# MAVBoard_Pro.net
KiCad netlist of a schematic drawn in EAGLE
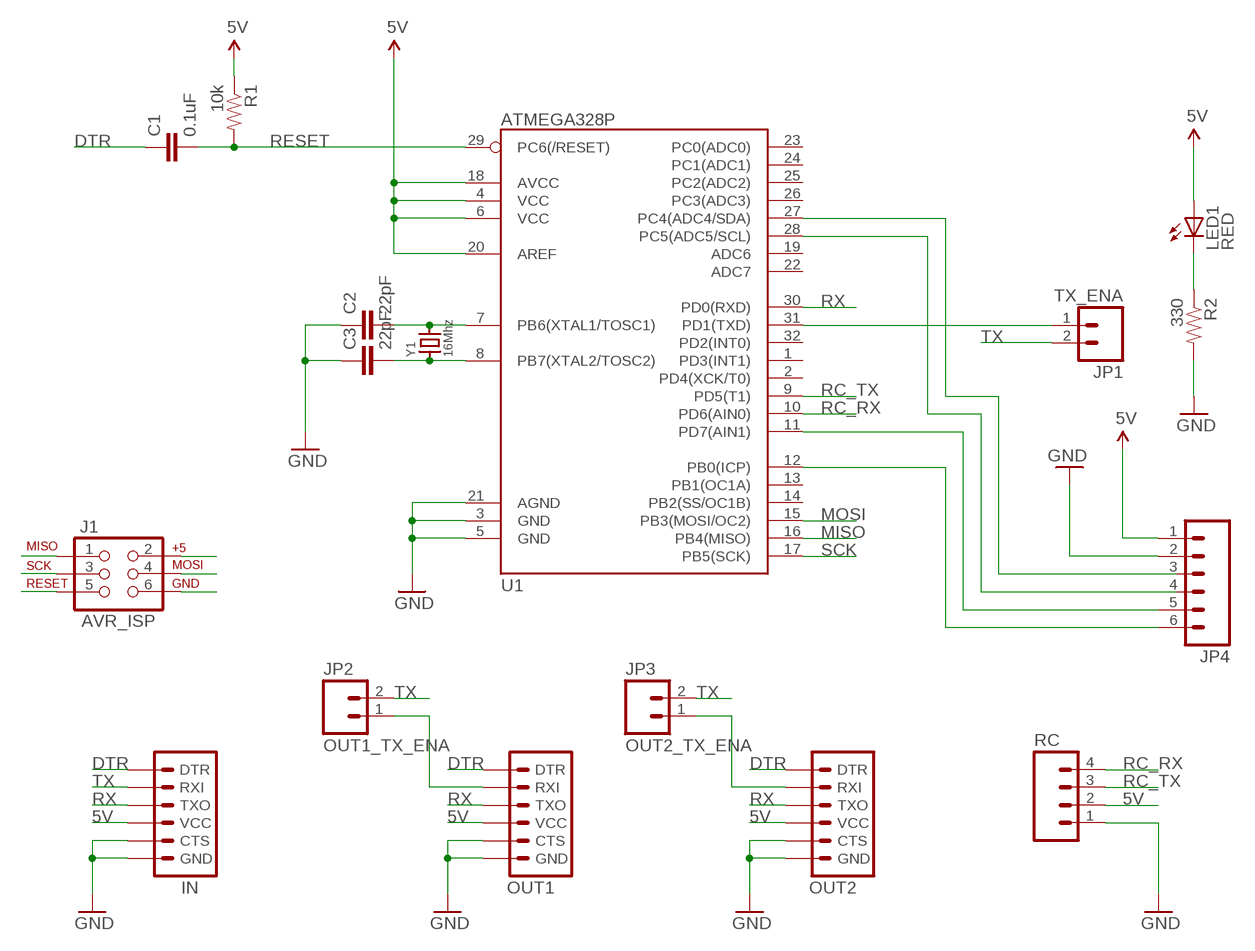
[diagram p0: schematic, sheet 1]

(export (version "E")
  (design (tool "Eeschema 10.0.6"))
  (components
    (comp (ref "C1")
      (value "0.1uF")
      (footprint "eagle-import:0603-CAP")
      (libsource (lib "eagle-import") (part "CAP0603-CAP"))
    )
    (comp (ref "C2")
      (value "22pF")
      (footprint "eagle-import:0603-CAP")
      (libsource (lib "eagle-import") (part "CAP0603-CAP"))
    )
    (comp (ref "C3")
      (value "22pF")
      (footprint "eagle-import:0603-CAP")
      (libsource (lib "eagle-import") (part "CAP0603-CAP"))
    )
    (comp (ref "IN")
      (value "ARDUINO_SERIAL_PROGRAMPTH")
      (footprint "eagle-import:1X06")
      (libsource (lib "eagle-import") (part "ARDUINO_SERIAL_PROGRAMPTH"))
    )
    (comp (ref "J1")
      (value "AVR_ISP")
      (footprint "eagle-import:2X3")
      (libsource (lib "eagle-import") (part "AVR_SPI_PRG_6PTH"))
    )
    (comp (ref "JP1")
      (value "TX_ENA")
      (footprint "eagle-import:1X02")
      (libsource (lib "eagle-import") (part "M02PTH"))
    )
    (comp (ref "JP2")
      (value "OUT1_TX_ENA")
      (footprint "eagle-import:1X02")
      (libsource (lib "eagle-import") (part "M02PTH"))
    )
    (comp (ref "JP3")
      (value "OUT2_TX_ENA")
      (footprint "eagle-import:1X02")
      (libsource (lib "eagle-import") (part "M02PTH"))
    )
    (comp (ref "JP4")
      (value "M06SIP")
      (footprint "eagle-import:1X06")
      (libsource (lib "eagle-import") (part "M06SIP"))
    )
    (comp (ref "LED1")
      (value "RED")
      (footprint "eagle-import:LED-0603")
      (libsource (lib "eagle-import") (part "LED0603"))
    )
    (comp (ref "OUT1")
      (value "ARDUINO_SERIAL_PROGRAMPTH")
      (footprint "eagle-import:1X06")
      (libsource (lib "eagle-import") (part "ARDUINO_SERIAL_PROGRAMPTH"))
    )
    (comp (ref "OUT2")
      (value "ARDUINO_SERIAL_PROGRAMPTH")
      (footprint "eagle-import:1X06")
      (libsource (lib "eagle-import") (part "ARDUINO_SERIAL_PROGRAMPTH"))
    )
    (comp (ref "R1")
      (value "10k")
      (footprint "eagle-import:0603-RES")
      (libsource (lib "eagle-import") (part "RESISTOR0603-RES"))
    )
    (comp (ref "R2")
      (value "330")
      (footprint "eagle-import:0603-RES")
      (libsource (lib "eagle-import") (part "RESISTOR0603-RES"))
    )
    (comp (ref "RC")
      (value "M04PTH")
      (footprint "eagle-import:1X04")
      (libsource (lib "eagle-import") (part "M04PTH"))
    )
    (comp (ref "U1")
      (value "ATMEGA328P")
      (footprint "eagle-import:TQFP32-08")
      (libsource (lib "eagle-import") (part "ATMEGA328_SMT"))
    )
    (comp (ref "Y1")
      (value "16Mhz")
      (footprint "eagle-import:CRYSTALSMD_5X3.2MM")
      (libsource (lib "eagle-import") (part "CRYSTAL5X3.2"))
    )
  )
  (nets
    (net (code "1") (name "/DTR") (class "Default")
      (node (ref "C1") (pin "1") (pinfunction "1_1") (pintype "passive"))
      (node (ref "IN") (pin "1") (pinfunction "DTR_1") (pintype "passive"))
      (node (ref "OUT1") (pin "1") (pinfunction "DTR_1") (pintype "passive"))
      (node (ref "OUT2") (pin "1") (pinfunction "DTR_1") (pintype "passive"))
    )
    (net (code "2") (name "/MISO") (class "Default")
      (node (ref "J1") (pin "1") (pinfunction "1_1") (pintype "passive"))
      (node (ref "U1") (pin "16") (pinfunction "PB4(MISO)_16") (pintype "bidirectional"))
    )
    (net (code "3") (name "/MOSI") (class "Default")
      (node (ref "J1") (pin "4") (pinfunction "4_4") (pintype "passive"))
      (node (ref "U1") (pin "15") (pinfunction "PB3(MOSI/OC2)_15") (pintype "bidirectional"))
    )
    (net (code "4") (name "/RC_RX") (class "Default")
      (node (ref "RC") (pin "4") (pinfunction "4_4") (pintype "passive"))
      (node (ref "U1") (pin "10") (pinfunction "PD6(AIN0)_10") (pintype "bidirectional"))
    )
    (net (code "5") (name "/RC_TX") (class "Default")
      (node (ref "RC") (pin "3") (pinfunction "3_3") (pintype "passive"))
      (node (ref "U1") (pin "9") (pinfunction "PD5(T1)_9") (pintype "bidirectional"))
    )
    (net (code "6") (name "/RESET") (class "Default")
      (node (ref "C1") (pin "2") (pinfunction "2_2") (pintype "passive"))
      (node (ref "J1") (pin "5") (pinfunction "5_5") (pintype "passive"))
      (node (ref "R1") (pin "2") (pinfunction "2_2") (pintype "passive"))
      (node (ref "U1") (pin "29") (pinfunction "PC6(/RESET)_29") (pintype "bidirectional"))
    )
    (net (code "7") (name "/RX") (class "Default")
      (node (ref "IN") (pin "3") (pinfunction "TXO_3") (pintype "passive"))
      (node (ref "OUT1") (pin "3") (pinfunction "TXO_3") (pintype "passive"))
      (node (ref "OUT2") (pin "3") (pinfunction "TXO_3") (pintype "passive"))
      (node (ref "U1") (pin "30") (pinfunction "PD0(RXD)_30") (pintype "bidirectional"))
    )
    (net (code "8") (name "/SCK") (class "Default")
      (node (ref "J1") (pin "3") (pinfunction "3_3") (pintype "passive"))
      (node (ref "U1") (pin "17") (pinfunction "PB5(SCK)_17") (pintype "bidirectional"))
    )
    (net (code "9") (name "/TX") (class "Default")
      (node (ref "IN") (pin "2") (pinfunction "RXI_2") (pintype "passive"))
      (node (ref "JP1") (pin "2") (pinfunction "2_2") (pintype "passive"))
      (node (ref "JP2") (pin "2") (pinfunction "2_2") (pintype "passive"))
      (node (ref "JP3") (pin "2") (pinfunction "2_2") (pintype "passive"))
    )
    (net (code "10") (name "5V") (class "Default")
      (node (ref "IN") (pin "4") (pinfunction "VCC_4") (pintype "passive"))
      (node (ref "J1") (pin "2") (pinfunction "2_2") (pintype "passive"))
      (node (ref "JP4") (pin "1") (pinfunction "1_1") (pintype "passive"))
      (node (ref "LED1") (pin "A") (pinfunction "A_A") (pintype "passive"))
      (node (ref "OUT1") (pin "4") (pinfunction "VCC_4") (pintype "passive"))
      (node (ref "OUT2") (pin "4") (pinfunction "VCC_4") (pintype "passive"))
      (node (ref "R1") (pin "1") (pinfunction "1_1") (pintype "passive"))
      (node (ref "RC") (pin "2") (pinfunction "2_2") (pintype "passive"))
      (node (ref "U1") (pin "18") (pinfunction "AVCC_18") (pintype "bidirectional"))
      (node (ref "U1") (pin "20") (pinfunction "AREF_20") (pintype "bidirectional"))
      (node (ref "U1") (pin "4") (pinfunction "VCC_4") (pintype "bidirectional"))
      (node (ref "U1") (pin "6") (pinfunction "VCC_6") (pintype "bidirectional"))
    )
    (net (code "11") (name "GND") (class "Default")
      (node (ref "C2") (pin "1") (pinfunction "1_1") (pintype "passive"))
      (node (ref "C3") (pin "1") (pinfunction "1_1") (pintype "passive"))
      (node (ref "IN") (pin "5") (pinfunction "CTS_5") (pintype "passive"))
      (node (ref "IN") (pin "6") (pinfunction "GND_6") (pintype "passive"))
      (node (ref "J1") (pin "6") (pinfunction "6_6") (pintype "passive"))
      (node (ref "JP4") (pin "2") (pinfunction "2_2") (pintype "passive"))
      (node (ref "OUT1") (pin "5") (pinfunction "CTS_5") (pintype "passive"))
      (node (ref "OUT1") (pin "6") (pinfunction "GND_6") (pintype "passive"))
      (node (ref "OUT2") (pin "5") (pinfunction "CTS_5") (pintype "passive"))
      (node (ref "OUT2") (pin "6") (pinfunction "GND_6") (pintype "passive"))
      (node (ref "R2") (pin "2") (pinfunction "2_2") (pintype "passive"))
      (node (ref "RC") (pin "1") (pinfunction "1_1") (pintype "passive"))
      (node (ref "U1") (pin "21") (pinfunction "AGND_21") (pintype "bidirectional"))
      (node (ref "U1") (pin "3") (pinfunction "GND_3") (pintype "bidirectional"))
      (node (ref "U1") (pin "5") (pinfunction "GND_5") (pintype "bidirectional"))
    )
    (net (code "12") (name "Net-(LED1-PadC)") (class "Default")
      (node (ref "LED1") (pin "C") (pinfunction "C_C") (pintype "passive"))
      (node (ref "R2") (pin "1") (pinfunction "1_1") (pintype "passive"))
    )
    (net (code "13") (name "Net-(OUT1-RXI)") (class "Default")
      (node (ref "JP2") (pin "1") (pinfunction "1_1") (pintype "passive"))
      (node (ref "OUT1") (pin "2") (pinfunction "RXI_2") (pintype "passive"))
    )
    (net (code "14") (name "Net-(OUT2-RXI)") (class "Default")
      (node (ref "JP3") (pin "1") (pinfunction "1_1") (pintype "passive"))
      (node (ref "OUT2") (pin "2") (pinfunction "RXI_2") (pintype "passive"))
    )
    (net (code "15") (name "Net-(U1-PB0(ICP))") (class "Default")
      (node (ref "JP4") (pin "6") (pinfunction "6_6") (pintype "passive"))
      (node (ref "U1") (pin "12") (pinfunction "PB0(ICP)_12") (pintype "bidirectional"))
    )
    (net (code "16") (name "Net-(U1-PB6(XTAL1{slash}TOSC1))") (class "Default")
      (node (ref "C2") (pin "2") (pinfunction "2_2") (pintype "passive"))
      (node (ref "U1") (pin "7") (pinfunction "PB6(XTAL1/TOSC1)_7") (pintype "bidirectional"))
      (node (ref "Y1") (pin "PIN3") (pinfunction "PIN3_PIN3") (pintype "bidirectional"))
    )
    (net (code "17") (name "Net-(U1-PB7(XTAL2{slash}TOSC2))") (class "Default")
      (node (ref "C3") (pin "2") (pinfunction "2_2") (pintype "passive"))
      (node (ref "U1") (pin "8") (pinfunction "PB7(XTAL2/TOSC2)_8") (pintype "bidirectional"))
      (node (ref "Y1") (pin "PIN1") (pinfunction "PIN1_PIN1") (pintype "bidirectional"))
    )
    (net (code "18") (name "Net-(U1-PC4(ADC4{slash}SDA))") (class "Default")
      (node (ref "JP4") (pin "3") (pinfunction "3_3") (pintype "passive"))
      (node (ref "U1") (pin "27") (pinfunction "PC4(ADC4/SDA)_27") (pintype "bidirectional"))
    )
    (net (code "19") (name "Net-(U1-PC5(ADC5{slash}SCL))") (class "Default")
      (node (ref "JP4") (pin "4") (pinfunction "4_4") (pintype "passive"))
      (node (ref "U1") (pin "28") (pinfunction "PC5(ADC5/SCL)_28") (pintype "bidirectional"))
    )
    (net (code "20") (name "Net-(U1-PD1(TXD))") (class "Default")
      (node (ref "JP1") (pin "1") (pinfunction "1_1") (pintype "passive"))
      (node (ref "U1") (pin "31") (pinfunction "PD1(TXD)_31") (pintype "bidirectional"))
    )
    (net (code "21") (name "Net-(U1-PD7(AIN1))") (class "Default")
      (node (ref "JP4") (pin "5") (pinfunction "5_5") (pintype "passive"))
      (node (ref "U1") (pin "11") (pinfunction "PD7(AIN1)_11") (pintype "bidirectional"))
    )
    (net (code "22") (name "unconnected-(U1-ADC6-Pad19)") (class "Default")
      (node (ref "U1") (pin "19") (pinfunction "ADC6_19") (pintype "bidirectional"))
    )
    (net (code "23") (name "unconnected-(U1-ADC7-Pad22)") (class "Default")
      (node (ref "U1") (pin "22") (pinfunction "ADC7_22") (pintype "bidirectional"))
    )
    (net (code "24") (name "unconnected-(U1-PB1(OC1A)-Pad13)") (class "Default")
      (node (ref "U1") (pin "13") (pinfunction "PB1(OC1A)_13") (pintype "bidirectional"))
    )
    (net (code "25") (name "unconnected-(U1-PB2(SS{slash}OC1B)-Pad14)") (class "Default")
      (node (ref "U1") (pin "14") (pinfunction "PB2(SS/OC1B)_14") (pintype "bidirectional"))
    )
    (net (code "26") (name "unconnected-(U1-PC0(ADC0)-Pad23)") (class "Default")
      (node (ref "U1") (pin "23") (pinfunction "PC0(ADC0)_23") (pintype "bidirectional"))
    )
    (net (code "27") (name "unconnected-(U1-PC1(ADC1)-Pad24)") (class "Default")
      (node (ref "U1") (pin "24") (pinfunction "PC1(ADC1)_24") (pintype "bidirectional"))
    )
    (net (code "28") (name "unconnected-(U1-PC2(ADC2)-Pad25)") (class "Default")
      (node (ref "U1") (pin "25") (pinfunction "PC2(ADC2)_25") (pintype "bidirectional"))
    )
    (net (code "29") (name "unconnected-(U1-PC3(ADC3)-Pad26)") (class "Default")
      (node (ref "U1") (pin "26") (pinfunction "PC3(ADC3)_26") (pintype "bidirectional"))
    )
    (net (code "30") (name "unconnected-(U1-PD2(INT0)-Pad32)") (class "Default")
      (node (ref "U1") (pin "32") (pinfunction "PD2(INT0)_32") (pintype "bidirectional"))
    )
    (net (code "31") (name "unconnected-(U1-PD3(INT1)-Pad1)") (class "Default")
      (node (ref "U1") (pin "1") (pinfunction "PD3(INT1)_1") (pintype "bidirectional"))
    )
    (net (code "32") (name "unconnected-(U1-PD4(XCK{slash}T0)-Pad2)") (class "Default")
      (node (ref "U1") (pin "2") (pinfunction "PD4(XCK/T0)_2") (pintype "bidirectional"))
    )
  )
)
